# nRF9160_Thing_Plus.net
KiCad netlist of a schematic drawn in EAGLE
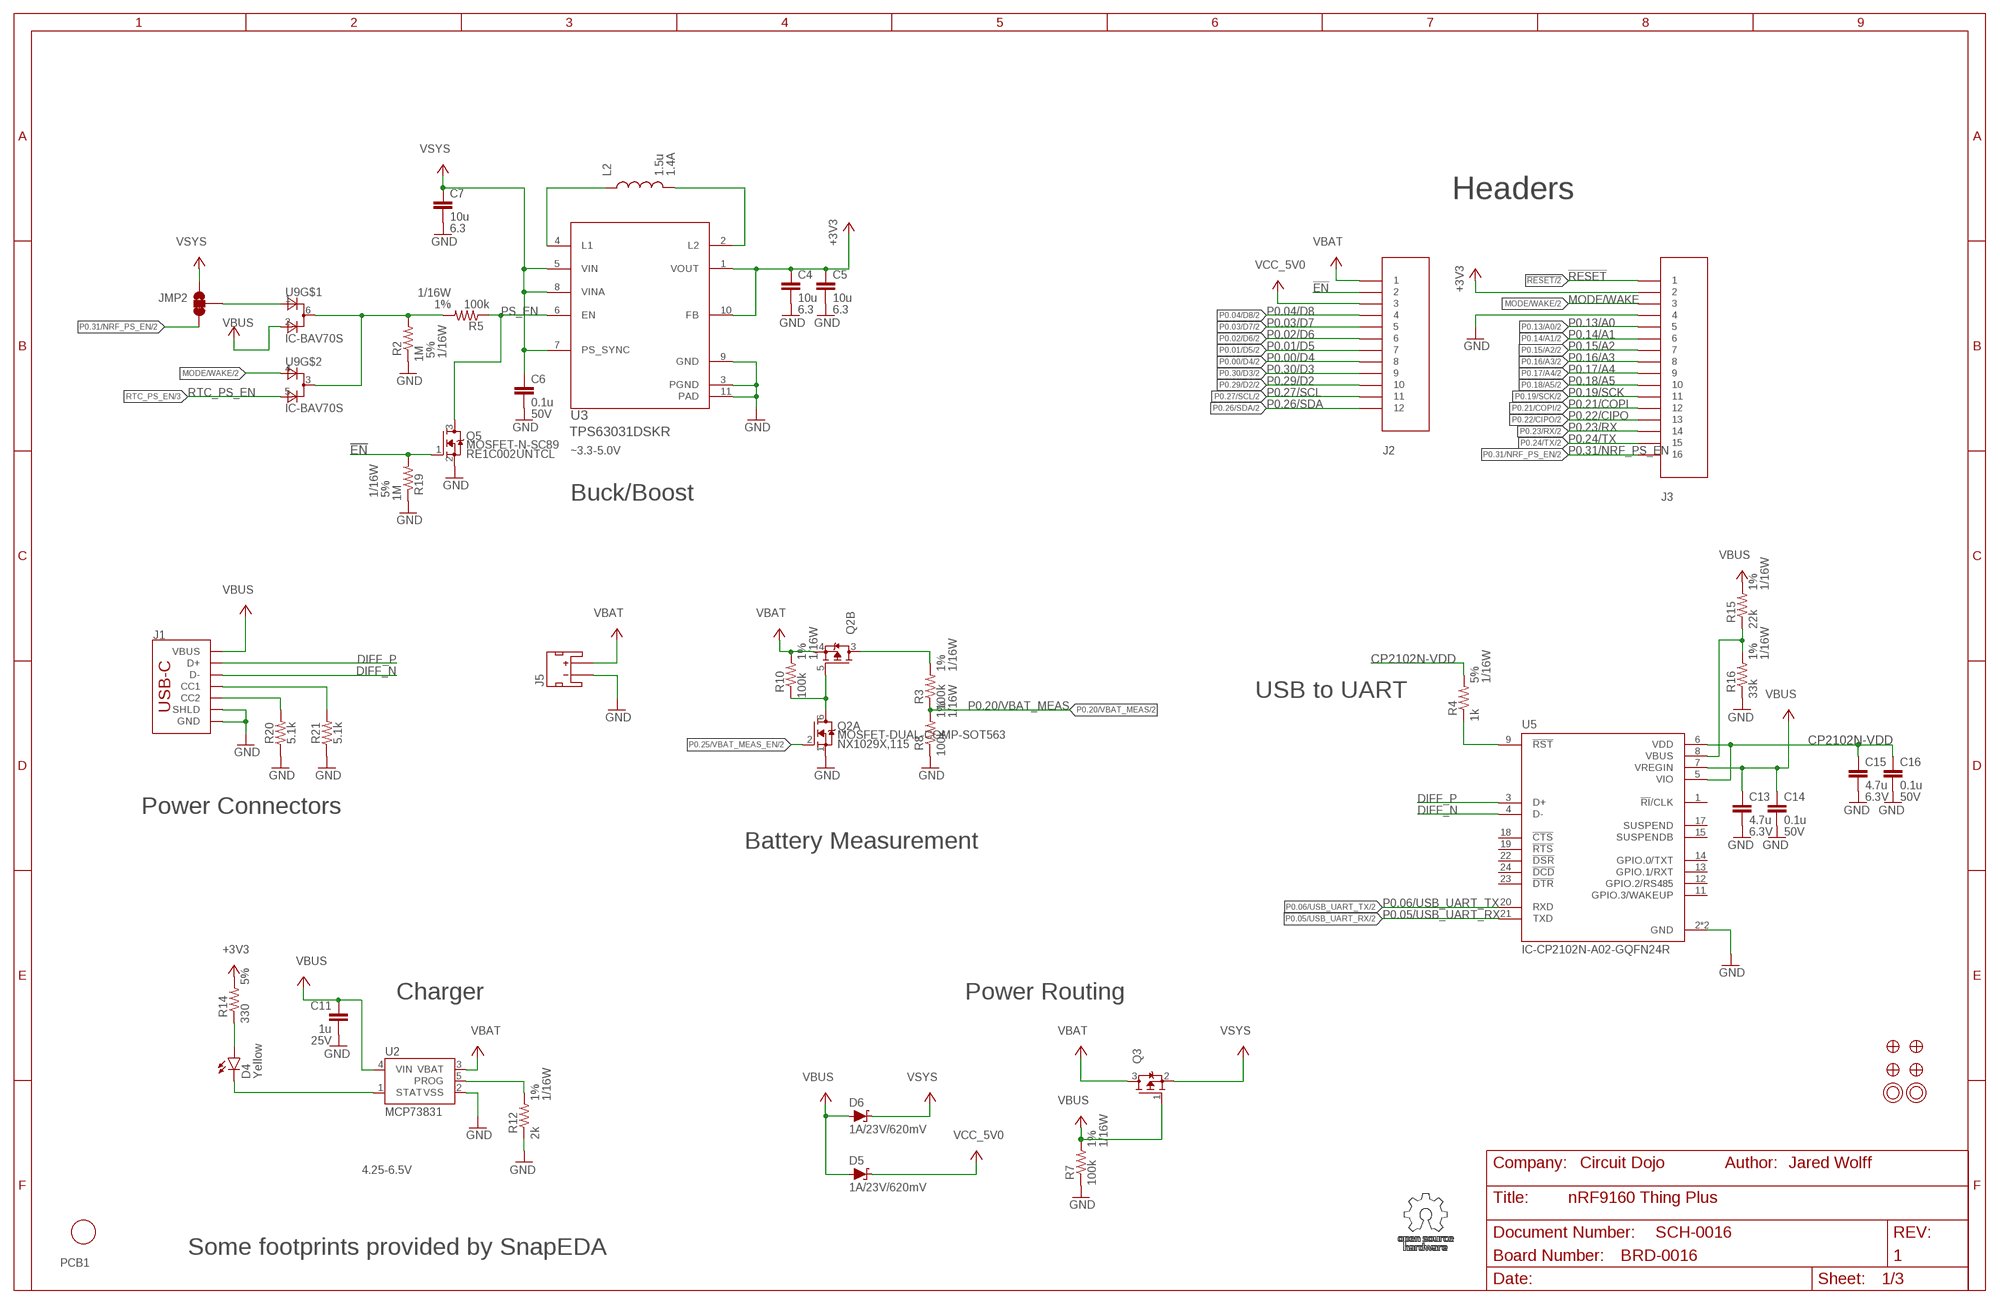
[diagram p0: schematic, sheet 1]
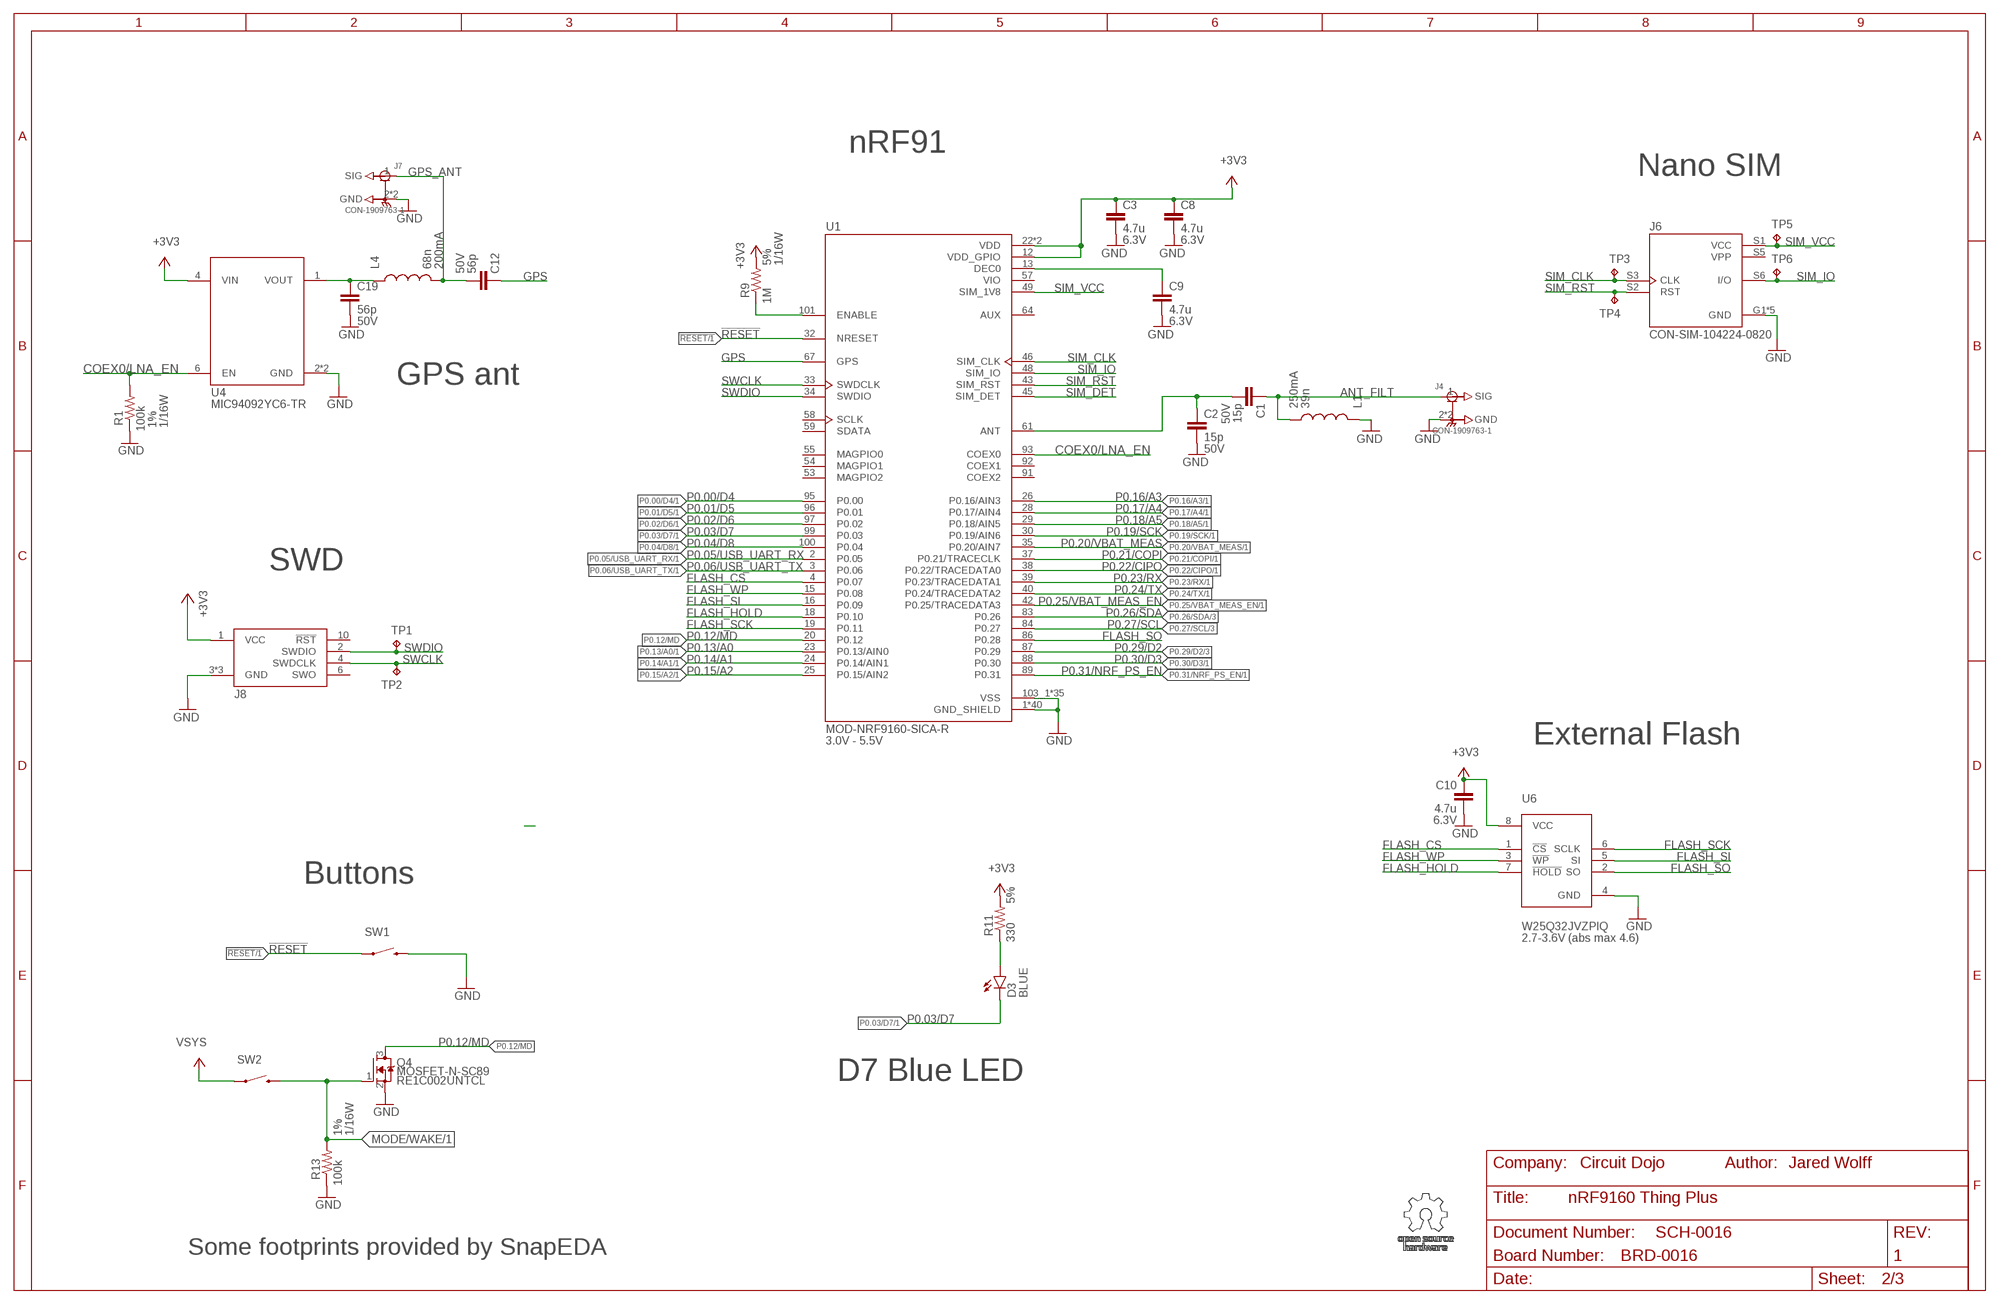
[diagram p1: schematic, sheet 2]
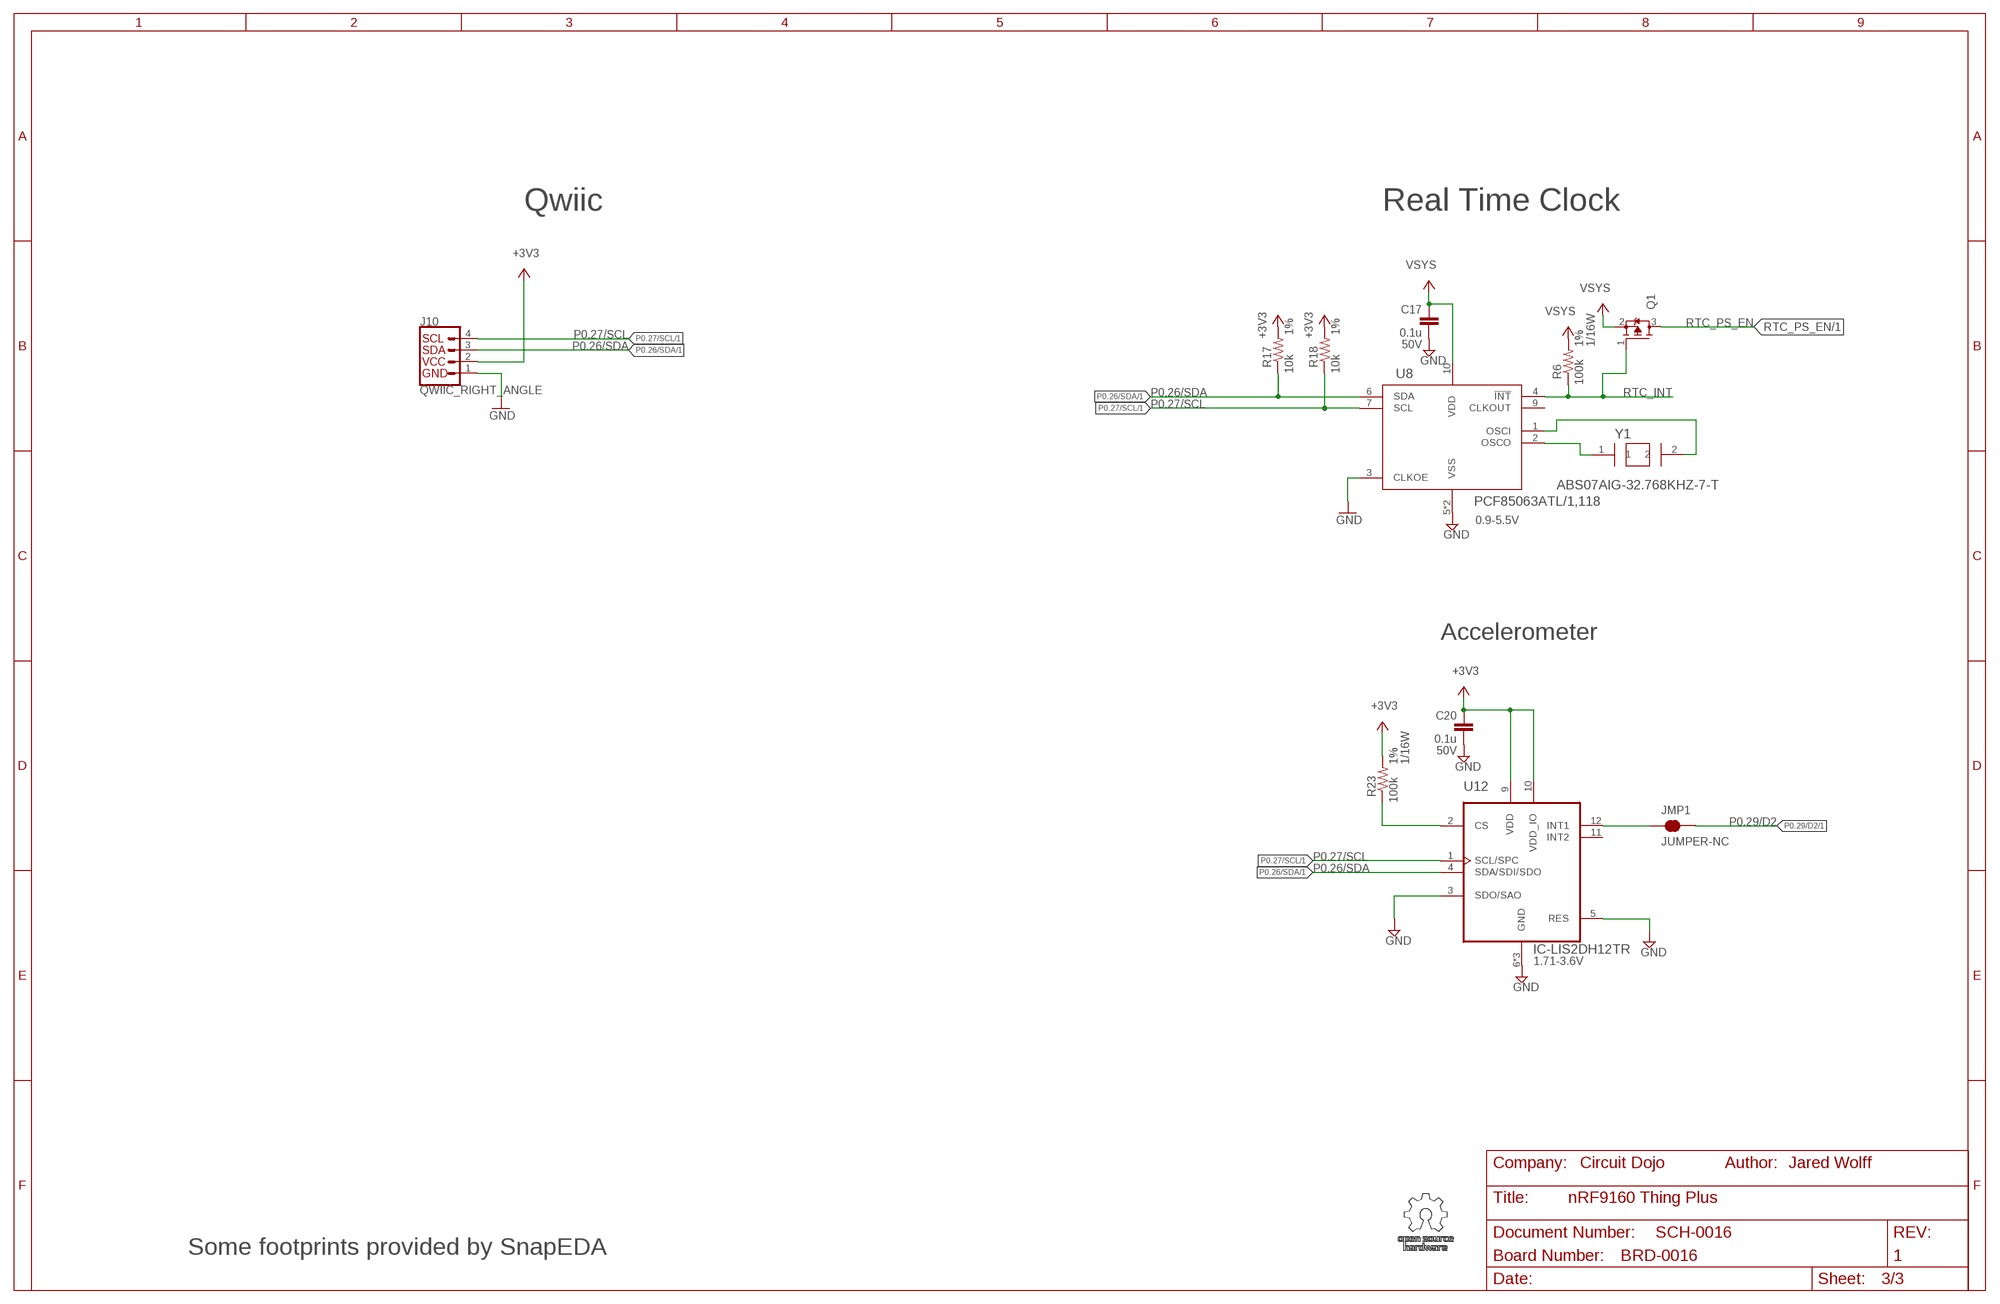
[diagram p2: schematic, sheet 3]

(export (version "E")
  (design (tool "Eeschema 10.0.6"))
  (components
    (comp (ref "C1")
      (value "15p")
      (footprint "eagle-import:CAPC1005X55N")
      (fields
        (field (name "MF") "Yageo")
        (field (name "MPN") "CC0402JRNPO9BN150")
        (field (name "VOLTHIGH") "50V")
      )
      (libsource (lib "eagle-import") (part "CAP-0402-15P-50V"))
    )
    (comp (ref "C2")
      (value "15p")
      (footprint "eagle-import:CAPC1005X55N")
      (fields
        (field (name "MF") "Yageo")
        (field (name "MPN") "CC0402JRNPO9BN150")
        (field (name "VOLTHIGH") "50V")
      )
      (libsource (lib "eagle-import") (part "CAP-0402-15P-50V"))
    )
    (comp (ref "C3")
      (value "4.7u")
      (footprint "eagle-import:C0603")
      (fields (field (name "MPN") "JMK107BB7475MA-T") (field (name "VOLTHIGH") "6.3V"))
      (libsource (lib "eagle-import") (part "CAP-0603-4.7U-6.3V-2"))
    )
    (comp (ref "C8")
      (value "4.7u")
      (footprint "eagle-import:C0603")
      (fields (field (name "MPN") "JMK107BB7475MA-T") (field (name "VOLTHIGH") "6.3V"))
      (libsource (lib "eagle-import") (part "CAP-0603-4.7U-6.3V-2"))
    )
    (comp (ref "C9")
      (value "4.7u")
      (footprint "eagle-import:C0603")
      (fields (field (name "MPN") "JMK107BB7475MA-T") (field (name "VOLTHIGH") "6.3V"))
      (libsource (lib "eagle-import") (part "CAP-0603-4.7U-6.3V-2"))
    )
    (comp (ref "C10")
      (value "4.7u")
      (footprint "eagle-import:C0603")
      (fields (field (name "MPN") "JMK107BB7475MA-T") (field (name "VOLTHIGH") "6.3V"))
      (libsource (lib "eagle-import") (part "CAP-0603-4.7U-6.3V-2"))
    )
    (comp (ref "C12")
      (value "56p")
      (footprint "eagle-import:CAPC1005X55N")
      (fields
        (field (name "MF") "Kemet")
        (field (name "MPN") "C0402C560J5GACTU‎")
        (field (name "VOLTHIGH") "50V")
      )
      (libsource (lib "eagle-import") (part "CAP-0402-56PF-50V"))
    )
    (comp (ref "C19")
      (value "56p")
      (footprint "eagle-import:CAPC1005X55N")
      (fields
        (field (name "MF") "Kemet")
        (field (name "MPN") "C0402C560J5GACTU‎")
        (field (name "VOLTHIGH") "50V")
      )
      (libsource (lib "eagle-import") (part "CAP-0402-56PF-50V"))
    )
    (comp (ref "D3")
      (value "BLUE")
      (footprint "eagle-import:LED-0603")
      (libsource (lib "eagle-import") (part "LED-BLUE0603"))
    )
    (comp (ref "J4")
      (value "CON-1909763-1")
      (footprint "eagle-import:TE_1909763-1")
      (fields (field (name "MF") "TE Connectivity") (field (name "MPN") "1909763-1"))
      (libsource (lib "eagle-import") (part "CON-1909763-1"))
    )
    (comp (ref "J6")
      (value "CON-SIM-104224-0820")
      (footprint "eagle-import:MOLEX_104224-0820")
      (fields (field (name "MF") "Molex") (field (name "MPN") "104224-0820"))
      (libsource (lib "eagle-import") (part "CON-SIM-104224-0820"))
    )
    (comp (ref "J7")
      (value "CON-1909763-1")
      (footprint "eagle-import:TE_1909763-1")
      (fields (field (name "MF") "TE Connectivity") (field (name "MPN") "1909763-1"))
      (libsource (lib "eagle-import") (part "CON-1909763-1"))
    )
    (comp (ref "J8")
      (value "CON-FTSH-105-XX-X-DV")
      (footprint "eagle-import:SAMTEC_FTSH-105-XX-X-DV")
      (fields (field (name "MF") "Samtec") (field (name "MPN") "FTSH-105-01-F-DV-K"))
      (libsource (lib "eagle-import") (part "CON-FTSH-105-XX-X-DV"))
    )
    (comp (ref "L1")
      (value "39n")
      (footprint "eagle-import:IND0402_22N_TAI")
      (fields (field (name "CURRENT") "250mA") (field (name "MPN") "LQG15HN39NJ02D"))
      (libsource (lib "eagle-import") (part "IND-0402-39NH-250MA"))
    )
    (comp (ref "L4")
      (value "68n")
      (footprint "eagle-import:IND0402_22N_TAI")
      (fields (field (name "CURRENT") "200mA") (field (name "MPN") "LQG15HN68NH02D‎"))
      (libsource (lib "eagle-import") (part "IND-0402-68NH-200MA"))
    )
    (comp (ref "Q4")
      (value "MOSFET-N-SC89")
      (footprint "eagle-import:DIO_RB558WMF-L")
      (fields (field (name "MPN") "RE1C002UNTCL") (field (name "MF") "Rohm Semiconductor"))
      (libsource (lib "eagle-import") (part "MOSFET-N-SC89"))
    )
    (comp (ref "R1")
      (value "100k")
      (footprint "eagle-import:R0402-M")
      (fields
        (field (name "MPN") "RC0402FR07100KL")
        (field (name "POWER") "1/16W")
        (field (name "TOLERANCE") "1%")
      )
      (libsource (lib "eagle-import") (part "RES-0402-100K-1%"))
    )
    (comp (ref "R9")
      (value "1M")
      (footprint "eagle-import:R0402-M")
      (fields
        (field (name "MPN") "RC0402JR-071ML")
        (field (name "POWER") "1/16W")
        (field (name "TOLERANCE") "5%")
      )
      (libsource (lib "eagle-import") (part "RES-0402-1M-5%"))
    )
    (comp (ref "R11")
      (value "330")
      (footprint "eagle-import:R0402-M")
      (fields
        (field (name "MF") "Yageo")
        (field (name "MPN") "RC0402JR-07330RL")
        (field (name "TOLERANCE") "5%")
      )
      (libsource (lib "eagle-import") (part "RES-0402-330-5%"))
    )
    (comp (ref "R13")
      (value "100k")
      (footprint "eagle-import:R0402-M")
      (fields
        (field (name "MPN") "RC0402FR07100KL")
        (field (name "POWER") "1/16W")
        (field (name "TOLERANCE") "1%")
      )
      (libsource (lib "eagle-import") (part "RES-0402-100K-1%"))
    )
    (comp (ref "SW1")
      (value "MOMENTARY-SWITCH-SPST-SMD-4.6X2.8MM")
      (footprint "eagle-import:TACTILE_SWITCH_SMD_4.6X2.8MM")
      (libsource (lib "eagle-import") (part "MOMENTARY-SWITCH-SPST-SMD-4.6X2.8MM"))
    )
    (comp (ref "SW2")
      (value "MOMENTARY-SWITCH-SPST-SMD-4.6X2.8MM")
      (footprint "eagle-import:TACTILE_SWITCH_SMD_4.6X2.8MM")
      (libsource (lib "eagle-import") (part "MOMENTARY-SWITCH-SPST-SMD-4.6X2.8MM"))
    )
    (comp (ref "TP1")
      (value "TP-1SIDE-1P0")
      (footprint "eagle-import:TP-1P0")
      (libsource (lib "eagle-import") (part "TP-1SIDE-1P0"))
    )
    (comp (ref "TP2")
      (value "TP-1SIDE-1P0")
      (footprint "eagle-import:TP-1P0")
      (libsource (lib "eagle-import") (part "TP-1SIDE-1P0"))
    )
    (comp (ref "TP3")
      (value "TP-1SIDE-1P0")
      (footprint "eagle-import:TP-1P0")
      (libsource (lib "eagle-import") (part "TP-1SIDE-1P0"))
    )
    (comp (ref "TP4")
      (value "TP-1SIDE-1P0")
      (footprint "eagle-import:TP-1P0")
      (libsource (lib "eagle-import") (part "TP-1SIDE-1P0"))
    )
    (comp (ref "TP5")
      (value "TP-1SIDE-1P0")
      (footprint "eagle-import:TP-1P0")
      (libsource (lib "eagle-import") (part "TP-1SIDE-1P0"))
    )
    (comp (ref "TP6")
      (value "TP-1SIDE-1P0")
      (footprint "eagle-import:TP-1P0")
      (libsource (lib "eagle-import") (part "TP-1SIDE-1P0"))
    )
    (comp (ref "U1")
      (value "MOD-NRF9160-SICA-R")
      (footprint "eagle-import:NORDIC_NRF9160-SICA-R")
      (fields (field (name "MF") "Nordic Semiconductor") (field (name "MPN") "NRF9160-SICA-R"))
      (libsource (lib "eagle-import") (part "MOD-NRF9160-SICA-R"))
    )
    (comp (ref "U4")
      (value "POWER-SWITCH-MIC94092YC6")
      (footprint "eagle-import:SOT363")
      (fields (field (name "MPN") "MIC94092YC6-TR"))
      (libsource (lib "eagle-import") (part "POWER-SWITCH-MIC94092YC6"))
    )
    (comp (ref "U6")
      (value "FLASH-WSON")
      (footprint "eagle-import:WIN_ZP-8-L")
      (fields (field (name "MPN") "W25Q32JVZPIQ"))
      (libsource (lib "eagle-import") (part "FLASH-WSON-W25Q32JVZPIQ"))
    )
    (comp (ref "C4")
      (value "10u")
      (footprint "eagle-import:C0603")
      (fields (field (name "MPN") "JMK107ABJ106MA-T") (field (name "VOLTHIGH") "6.3"))
      (libsource (lib "eagle-import") (part "CAP-0603-10U-6.3V"))
    )
    (comp (ref "C5")
      (value "10u")
      (footprint "eagle-import:C0603")
      (fields (field (name "MPN") "JMK107ABJ106MA-T") (field (name "VOLTHIGH") "6.3"))
      (libsource (lib "eagle-import") (part "CAP-0603-10U-6.3V"))
    )
    (comp (ref "C6")
      (value "0.1u")
      (footprint "eagle-import:CAPC1005X55N")
      (fields
        (field (name "MF") "Taiyo Yuden")
        (field (name "MPN") "UMK105BJ104KV-F")
        (field (name "VOLTHIGH") "50V")
      )
      (libsource (lib "eagle-import") (part "CAP-0402-0.1U-50V"))
    )
    (comp (ref "C7")
      (value "10u")
      (footprint "eagle-import:C0603")
      (fields (field (name "MPN") "JMK107ABJ106MA-T") (field (name "VOLTHIGH") "6.3"))
      (libsource (lib "eagle-import") (part "CAP-0603-10U-6.3V"))
    )
    (comp (ref "C11")
      (value "1u")
      (footprint "eagle-import:CAPC1005X55N")
      (fields
        (field (name "MF") "TDK")
        (field (name "MPN") "C1005X5R1E105M050BC")
        (field (name "VOLTHIGH") "25V")
      )
      (libsource (lib "eagle-import") (part "CAP-0402-1U-25V-1"))
    )
    (comp (ref "C13")
      (value "4.7u")
      (footprint "eagle-import:C0603")
      (fields (field (name "MPN") "JMK107BB7475MA-T") (field (name "VOLTHIGH") "6.3V"))
      (libsource (lib "eagle-import") (part "CAP-0603-4.7U-6.3V-2"))
    )
    (comp (ref "C14")
      (value "0.1u")
      (footprint "eagle-import:CAPC1005X55N")
      (fields
        (field (name "MF") "Taiyo Yuden")
        (field (name "MPN") "UMK105BJ104KV-F")
        (field (name "VOLTHIGH") "50V")
      )
      (libsource (lib "eagle-import") (part "CAP-0402-0.1U-50V"))
    )
    (comp (ref "C15")
      (value "4.7u")
      (footprint "eagle-import:C0603")
      (fields (field (name "MPN") "JMK107BB7475MA-T") (field (name "VOLTHIGH") "6.3V"))
      (libsource (lib "eagle-import") (part "CAP-0603-4.7U-6.3V-2"))
    )
    (comp (ref "C16")
      (value "0.1u")
      (footprint "eagle-import:CAPC1005X55N")
      (fields
        (field (name "MF") "Taiyo Yuden")
        (field (name "MPN") "UMK105BJ104KV-F")
        (field (name "VOLTHIGH") "50V")
      )
      (libsource (lib "eagle-import") (part "CAP-0402-0.1U-50V"))
    )
    (comp (ref "D4")
      (value "Yellow")
      (footprint "eagle-import:LED-0603")
      (libsource (lib "eagle-import") (part "LED-YELLOW0603"))
    )
    (comp (ref "D5")
      (value "1A/23V/620mV")
      (footprint "eagle-import:SOD-323")
      (libsource (lib "eagle-import") (part "DIODE-SCHOTTKY-BAT20J"))
    )
    (comp (ref "D6")
      (value "1A/23V/620mV")
      (footprint "eagle-import:SOD-323")
      (libsource (lib "eagle-import") (part "DIODE-SCHOTTKY-BAT20J"))
    )
    (comp (ref "J1")
      (value "USB Female C")
      (footprint "eagle-import:USB-C-16P_4LAYER-PADS")
      (libsource (lib "eagle-import") (part "USB_C_4-LAYER_PADS"))
    )
    (comp (ref "J2")
      (value "CON-HEADER-1X12-MALE-PIN")
      (footprint "eagle-import:CON-HEADER-1X12-MALE-PIN")
      (libsource (lib "eagle-import") (part "CON-HEADER-1X12-MALE-PIN"))
    )
    (comp (ref "J3")
      (value "CON-HEADER-1X16-MALE-PIN")
      (footprint "eagle-import:CON-HEADER-1X16-MALE-PIN")
      (libsource (lib "eagle-import") (part "CON-HEADER-1X16-MALE-PIN"))
    )
    (comp (ref "J5")
      (value "JST_2MM_MALE")
      (footprint "eagle-import:JST-2-SMD")
      (libsource (lib "eagle-import") (part "JST_2MM_MALE"))
    )
    (comp (ref "JMP2")
      (value "JUMPER-3/1")
      (footprint "eagle-import:JUMPER-ROUND-3-NO-R")
      (libsource (lib "eagle-import") (part "JUMPER-3/1"))
    )
    (comp (ref "L2")
      (value "1.5u")
      (footprint "eagle-import:IND-2P0X2P0X1P2")
      (fields (field (name "CURRENT") "1.4A") (field (name "MPN") "NRV2012T1R5NGF"))
      (libsource (lib "eagle-import") (part "IND-1.5U-1.4A-2X2"))
    )
    (comp (ref "PCB1")
      (value "PCB-NRF91-FEATHER")
      (footprint "eagle-import:PLACEHOLDER")
      (fields (field (name "MPN") "BRD-0015"))
      (libsource (lib "eagle-import") (part "PCB-NRF91-FEATHER"))
    )
    (comp (ref "Q2")
      (value "MOSFET-DUAL-COMP-SOT563")
      (footprint "eagle-import:SOT50P160X60-6N")
      (fields (field (name "MPN") "NX1029X,115"))
      (libsource (lib "eagle-import") (part "MOSFET-DUAL-COMP-SOT563"))
    )
    (comp (ref "Q3")
      (value "MOSFET-P-20V-4.7A-SOT23")
      (footprint "eagle-import:SOT23")
      (fields (field (name "MPN") "TSM500P02CX RFG"))
      (libsource (lib "eagle-import") (part "MOSFET-P-SOT23-20V-4.7A"))
    )
    (comp (ref "Q5")
      (value "MOSFET-N-SC89")
      (footprint "eagle-import:DIO_RB558WMF-L")
      (fields (field (name "MPN") "RE1C002UNTCL") (field (name "MF") "Rohm Semiconductor"))
      (libsource (lib "eagle-import") (part "MOSFET-N-SC89"))
    )
    (comp (ref "R2")
      (value "1M")
      (footprint "eagle-import:R0402-M")
      (fields
        (field (name "MPN") "RC0402JR-071ML")
        (field (name "POWER") "1/16W")
        (field (name "TOLERANCE") "5%")
      )
      (libsource (lib "eagle-import") (part "RES-0402-1M-5%"))
    )
    (comp (ref "R3")
      (value "100k")
      (footprint "eagle-import:R0402-M")
      (fields
        (field (name "MPN") "RC0402FR07100KL")
        (field (name "POWER") "1/16W")
        (field (name "TOLERANCE") "1%")
      )
      (libsource (lib "eagle-import") (part "RES-0402-100K-1%"))
    )
    (comp (ref "R4")
      (value "1k")
      (footprint "eagle-import:R0402-M")
      (fields
        (field (name "MPN") "RC0402JR-071KL")
        (field (name "POWER") "1/16W")
        (field (name "TOLERANCE") "5%")
      )
      (libsource (lib "eagle-import") (part "RES-0402-1K-5%"))
    )
    (comp (ref "R5")
      (value "100k")
      (footprint "eagle-import:R0402-M")
      (fields
        (field (name "MPN") "RC0402FR07100KL")
        (field (name "POWER") "1/16W")
        (field (name "TOLERANCE") "1%")
      )
      (libsource (lib "eagle-import") (part "RES-0402-100K-1%"))
    )
    (comp (ref "R7")
      (value "100k")
      (footprint "eagle-import:R0402-M")
      (fields
        (field (name "MPN") "RC0402FR07100KL")
        (field (name "POWER") "1/16W")
        (field (name "TOLERANCE") "1%")
      )
      (libsource (lib "eagle-import") (part "RES-0402-100K-1%"))
    )
    (comp (ref "R8")
      (value "100k")
      (footprint "eagle-import:R0402-M")
      (fields
        (field (name "MPN") "RC0402FR07100KL")
        (field (name "POWER") "1/16W")
        (field (name "TOLERANCE") "1%")
      )
      (libsource (lib "eagle-import") (part "RES-0402-100K-1%"))
    )
    (comp (ref "R10")
      (value "100k")
      (footprint "eagle-import:R0402-M")
      (fields
        (field (name "MPN") "RC0402FR07100KL")
        (field (name "POWER") "1/16W")
        (field (name "TOLERANCE") "1%")
      )
      (libsource (lib "eagle-import") (part "RES-0402-100K-1%"))
    )
    (comp (ref "R12")
      (value "2k")
      (footprint "eagle-import:R0402-M")
      (fields
        (field (name "MPN") "RC0402FR-072KL")
        (field (name "POWER") "1/16W")
        (field (name "TOLERANCE") "1%")
      )
      (libsource (lib "eagle-import") (part "RES-0402-2K-1%"))
    )
    (comp (ref "R14")
      (value "330")
      (footprint "eagle-import:R0402-M")
      (fields
        (field (name "MF") "Yageo")
        (field (name "MPN") "RC0402JR-07330RL")
        (field (name "TOLERANCE") "5%")
      )
      (libsource (lib "eagle-import") (part "RES-0402-330-5%"))
    )
    (comp (ref "R15")
      (value "22k")
      (footprint "eagle-import:R0402-M")
      (fields
        (field (name "MF") "Yageo")
        (field (name "MPN") "RC0402FR-0722KL")
        (field (name "POWER") "1/16W")
        (field (name "TOLERANCE") "1%")
      )
      (libsource (lib "eagle-import") (part "RES-0402-22K-1%"))
    )
    (comp (ref "R16")
      (value "33k")
      (footprint "eagle-import:R0402-M")
      (fields
        (field (name "MF") "Yageo")
        (field (name "MPN") "RC0402FR-0722KL")
        (field (name "POWER") "1/16W")
        (field (name "TOLERANCE") "1%")
      )
      (libsource (lib "eagle-import") (part "RES-0402-33K-1%"))
    )
    (comp (ref "R19")
      (value "1M")
      (footprint "eagle-import:R0402-M")
      (fields
        (field (name "MPN") "RC0402JR-071ML")
        (field (name "POWER") "1/16W")
        (field (name "TOLERANCE") "5%")
      )
      (libsource (lib "eagle-import") (part "RES-0402-1M-5%"))
    )
    (comp (ref "R20")
      (value "5.1k")
      (footprint "eagle-import:0402-TIGHT")
      (libsource (lib "eagle-import") (part "5.1KOHM-0402T-1/16W-1%"))
    )
    (comp (ref "R21")
      (value "5.1k")
      (footprint "eagle-import:0402-TIGHT")
      (libsource (lib "eagle-import") (part "5.1KOHM-0402T-1/16W-1%"))
    )
    (comp (ref "U$3")
      (value "FIDUCIAL-1MM")
      (footprint "eagle-import:FIDUCIAL-1MM")
      (libsource (lib "eagle-import") (part "FIDUCIAL-1MM"))
    )
    (comp (ref "U$4")
      (value "FIDUCIAL-1MM")
      (footprint "eagle-import:FIDUCIAL-1MM")
      (libsource (lib "eagle-import") (part "FIDUCIAL-1MM"))
    )
    (comp (ref "U$24")
      (value "FIDUCIAL-1MM")
      (footprint "eagle-import:FIDUCIAL-1MM")
      (libsource (lib "eagle-import") (part "FIDUCIAL-1MM"))
    )
    (comp (ref "U$31")
      (value "MOUNTING-HOLE-2.5MM-PLATED")
      (footprint "eagle-import:MOUNTING-HOLE-2.5MM-PLATED")
      (libsource (lib "eagle-import") (part "MOUNTING-HOLE-2.5MM-PLATED"))
    )
    (comp (ref "U$32")
      (value "MOUNTING-HOLE-2.5MM-PLATED")
      (footprint "eagle-import:MOUNTING-HOLE-2.5MM-PLATED")
      (libsource (lib "eagle-import") (part "MOUNTING-HOLE-2.5MM-PLATED"))
    )
    (comp (ref "U$35")
      (value "FIDUCIAL-1MM")
      (footprint "eagle-import:FIDUCIAL-1MM")
      (libsource (lib "eagle-import") (part "FIDUCIAL-1MM"))
    )
    (comp (ref "U2")
      (value "MCP73831")
      (footprint "eagle-import:SOT23-5")
      (libsource (lib "eagle-import") (part "MCP73831"))
    )
    (comp (ref "U3")
      (value "IC-TPS63031DSKR")
      (footprint "eagle-import:DSK0010A")
      (fields (field (name "MF") "Texas Instruments") (field (name "MPN") "TPS63031DSKR"))
      (libsource (lib "eagle-import") (part "IC-TPS63031DSKR"))
    )
    (comp (ref "U5")
      (value "IC-CP2102N-A02-GQFN24R")
      (footprint "eagle-import:QFN50P400X400X80-25N")
      (fields (field (name "MF") "Silicon Labs") (field (name "MPN") "CP2102N-A02-GQFN24R"))
      (libsource (lib "eagle-import") (part "IC-CP2102N-A02-GQFN24R"))
    )
    (comp (ref "U9")
      (value "IC-BAV70S")
      (footprint "eagle-import:SOT363")
      (fields (field (name "MF") "Nexperia USA Inc.") (field (name "MPN") "BAV70S,115"))
      (libsource (lib "eagle-import") (part "IC-BAV70S"))
    )
    (comp (ref "C17")
      (value "0.1u")
      (footprint "eagle-import:CAPC1005X55N")
      (fields
        (field (name "MF") "Taiyo Yuden")
        (field (name "MPN") "UMK105BJ104KV-F")
        (field (name "VOLTHIGH") "50V")
      )
      (libsource (lib "eagle-import") (part "CAP-0402-0.1U-50V"))
    )
    (comp (ref "C20")
      (value "0.1u")
      (footprint "eagle-import:CAPC1005X55N")
      (fields
        (field (name "MF") "Taiyo Yuden")
        (field (name "MPN") "UMK105BJ104KV-F")
        (field (name "VOLTHIGH") "50V")
      )
      (libsource (lib "eagle-import") (part "CAP-0402-0.1U-50V"))
    )
    (comp (ref "J10")
      (value "QWIIC_RIGHT_ANGLE")
      (footprint "eagle-import:JST04_1MM_RA")
      (libsource (lib "eagle-import") (part "QWIIC_CONNECTORJS-1MM"))
    )
    (comp (ref "JMP1")
      (value "JUMPER-NC")
      (footprint "eagle-import:JUMPER-ROUND-NC")
      (libsource (lib "eagle-import") (part "JUMPER-NC"))
    )
    (comp (ref "Q1")
      (value "MOSFET-P-SC89")
      (footprint "eagle-import:DIO_RB558WMF-L")
      (fields (field (name "MPN") "RE1C001ZPTL"))
      (libsource (lib "eagle-import") (part "MOSFET-P-SC89"))
    )
    (comp (ref "R6")
      (value "100k")
      (footprint "eagle-import:R0402-M")
      (fields
        (field (name "MPN") "RC0402FR07100KL")
        (field (name "POWER") "1/16W")
        (field (name "TOLERANCE") "1%")
      )
      (libsource (lib "eagle-import") (part "RES-0402-100K-1%"))
    )
    (comp (ref "R17")
      (value "10k")
      (footprint "eagle-import:R0402-M")
      (fields (field (name "MPN") "RC0603FR-0710KL") (field (name "TOLERANCE") "1%"))
      (libsource (lib "eagle-import") (part "RES-0402-10K-1%"))
    )
    (comp (ref "R18")
      (value "10k")
      (footprint "eagle-import:R0402-M")
      (fields (field (name "MPN") "RC0603FR-0710KL") (field (name "TOLERANCE") "1%"))
      (libsource (lib "eagle-import") (part "RES-0402-10K-1%"))
    )
    (comp (ref "R23")
      (value "100k")
      (footprint "eagle-import:R0402-M")
      (fields
        (field (name "MPN") "RC0402FR07100KL")
        (field (name "POWER") "1/16W")
        (field (name "TOLERANCE") "1%")
      )
      (libsource (lib "eagle-import") (part "RES-0402-100K-1%"))
    )
    (comp (ref "U8")
      (value "IC-PCF85063ATL/1")
      (footprint "eagle-import:DFN10_2P7X2P7-L")
      (fields (field (name "MPN") "PCF85063ATL/1,118") (field (name "MF") "NXP"))
      (libsource (lib "eagle-import") (part "IC-PCF85063ATL/1"))
    )
    (comp (ref "U12")
      (value "IC-LIS2DH12TR")
      (footprint "eagle-import:PQFN50P200X200100-12N")
      (fields (field (name "MF") "STMicroelectronics") (field (name "MPN") "LIS2DH12TR"))
      (libsource (lib "eagle-import") (part "IC-LIS2DH12TR"))
    )
    (comp (ref "Y1")
      (value "XTAL-ABS07AIG-32.768KHZ-7-T")
      (footprint "eagle-import:XTAL320X150X90")
      (fields (field (name "MPN") "ABS07AIG-32.768KHZ-7-T") (field (name "MF") "Abracon"))
      (libsource (lib "eagle-import") (part "XTAL-ABS07AIG-32.768KHZ-7-T"))
    )
  )
  (nets
    (net (code "1") (name "+3V3") (class "Default")
      (node (ref "C10") (pin "1") (pinfunction "1_1") (pintype "passive"))
      (node (ref "C20") (pin "1") (pinfunction "1_1") (pintype "passive"))
      (node (ref "C3") (pin "1") (pinfunction "1_1") (pintype "passive"))
      (node (ref "C4") (pin "1") (pinfunction "1_1") (pintype "passive"))
      (node (ref "C5") (pin "1") (pinfunction "1_1") (pintype "passive"))
      (node (ref "C8") (pin "1") (pinfunction "1_1") (pintype "passive"))
      (node (ref "J10") (pin "2") (pinfunction "2_2") (pintype "power_in"))
      (node (ref "J3") (pin "2") (pinfunction "2_2") (pintype "bidirectional"))
      (node (ref "J8") (pin "1") (pinfunction "VCC_1") (pintype "bidirectional"))
      (node (ref "R11") (pin "2") (pinfunction "2_2") (pintype "passive"))
      (node (ref "R14") (pin "2") (pinfunction "2_2") (pintype "passive"))
      (node (ref "R17") (pin "2") (pinfunction "2_2") (pintype "passive"))
      (node (ref "R18") (pin "2") (pinfunction "2_2") (pintype "passive"))
      (node (ref "R23") (pin "2") (pinfunction "2_2") (pintype "passive"))
      (node (ref "R9") (pin "2") (pinfunction "2_2") (pintype "passive"))
      (node (ref "U1") (pin "102") (pinfunction "VDD_102") (pintype "power_in"))
      (node (ref "U1") (pin "12") (pinfunction "VDD_GPIO_12") (pintype "power_in"))
      (node (ref "U1") (pin "22") (pinfunction "VDD_22") (pintype "power_in"))
      (node (ref "U12") (pin "10") (pinfunction "VDD_IO_10") (pintype "power_in"))
      (node (ref "U12") (pin "9") (pinfunction "VDD_9") (pintype "power_in"))
      (node (ref "U3") (pin "1") (pinfunction "VOUT_1") (pintype "power_in"))
      (node (ref "U3") (pin "10") (pinfunction "FB_10") (pintype "input"))
      (node (ref "U4") (pin "4") (pinfunction "VIN_4") (pintype "power_in"))
      (node (ref "U6") (pin "8") (pinfunction "VCC_8") (pintype "bidirectional"))
    )
    (net (code "2") (name "ANT_FILT") (class "Default")
      (node (ref "C1") (pin "1") (pinfunction "1_1") (pintype "passive"))
      (node (ref "J4") (pin "1") (pinfunction "SIG_1") (pintype "passive"))
      (node (ref "L1") (pin "2") (pinfunction "2_2") (pintype "passive"))
    )
    (net (code "3") (name "COEX0{slash}LNA_EN") (class "Default")
      (node (ref "R1") (pin "2") (pinfunction "2_2") (pintype "passive"))
      (node (ref "U1") (pin "93") (pinfunction "COEX0_93") (pintype "bidirectional"))
      (node (ref "U4") (pin "6") (pinfunction "EN_6") (pintype "input"))
    )
    (net (code "4") (name "CP2102N-VDD") (class "Default")
      (node (ref "C15") (pin "1") (pinfunction "1_1") (pintype "passive"))
      (node (ref "C16") (pin "1") (pinfunction "1_1") (pintype "passive"))
      (node (ref "R4") (pin "2") (pinfunction "2_2") (pintype "passive"))
      (node (ref "U5") (pin "5") (pinfunction "VIO_5") (pintype "power_in"))
      (node (ref "U5") (pin "6") (pinfunction "VDD_6") (pintype "power_in"))
    )
    (net (code "5") (name "DIFF_N") (class "Default")
      (node (ref "J1") (pin "A7") (pinfunction "D-_A7") (pintype "bidirectional"))
      (node (ref "J1") (pin "B7") (pinfunction "D-_B7") (pintype "bidirectional"))
      (node (ref "U5") (pin "4") (pinfunction "D-_4") (pintype "bidirectional"))
    )
    (net (code "6") (name "DIFF_P") (class "Default")
      (node (ref "J1") (pin "A6") (pinfunction "D+_A6") (pintype "bidirectional"))
      (node (ref "J1") (pin "B6") (pinfunction "D+_B6") (pintype "bidirectional"))
      (node (ref "U5") (pin "3") (pinfunction "D+_3") (pintype "bidirectional"))
    )
    (net (code "7") (name "FLASH_CS") (class "Default")
      (node (ref "U1") (pin "4") (pinfunction "P0.07_4") (pintype "bidirectional"))
      (node (ref "U6") (pin "1") (pinfunction "~{CS}_1") (pintype "bidirectional"))
    )
    (net (code "8") (name "FLASH_HOLD") (class "Default")
      (node (ref "U1") (pin "18") (pinfunction "P0.10_18") (pintype "bidirectional"))
      (node (ref "U6") (pin "7") (pinfunction "~{HOLD}_7") (pintype "bidirectional"))
    )
    (net (code "9") (name "FLASH_SCK") (class "Default")
      (node (ref "U1") (pin "19") (pinfunction "P0.11_19") (pintype "bidirectional"))
      (node (ref "U6") (pin "6") (pinfunction "SCLK_6") (pintype "bidirectional"))
    )
    (net (code "10") (name "FLASH_SI") (class "Default")
      (node (ref "U1") (pin "16") (pinfunction "P0.09_16") (pintype "bidirectional"))
      (node (ref "U6") (pin "5") (pinfunction "SI_5") (pintype "bidirectional"))
    )
    (net (code "11") (name "FLASH_SO") (class "Default")
      (node (ref "U1") (pin "86") (pinfunction "P0.28_86") (pintype "bidirectional"))
      (node (ref "U6") (pin "2") (pinfunction "SO_2") (pintype "bidirectional"))
    )
    (net (code "12") (name "FLASH_WP") (class "Default")
      (node (ref "U1") (pin "15") (pinfunction "P0.08_15") (pintype "bidirectional"))
      (node (ref "U6") (pin "3") (pinfunction "~{WP}_3") (pintype "bidirectional"))
    )
    (net (code "13") (name "GND") (class "Default")
      (node (ref "C10") (pin "2") (pinfunction "2_2") (pintype "passive"))
      (node (ref "C11") (pin "2") (pinfunction "2_2") (pintype "passive"))
      (node (ref "C13") (pin "2") (pinfunction "2_2") (pintype "passive"))
      (node (ref "C14") (pin "2") (pinfunction "2_2") (pintype "passive"))
      (node (ref "C15") (pin "2") (pinfunction "2_2") (pintype "passive"))
      (node (ref "C16") (pin "2") (pinfunction "2_2") (pintype "passive"))
      (node (ref "C17") (pin "2") (pinfunction "2_2") (pintype "passive"))
      (node (ref "C19") (pin "2") (pinfunction "2_2") (pintype "passive"))
      (node (ref "C2") (pin "2") (pinfunction "2_2") (pintype "passive"))
      (node (ref "C20") (pin "2") (pinfunction "2_2") (pintype "passive"))
      (node (ref "C3") (pin "2") (pinfunction "2_2") (pintype "passive"))
      (node (ref "C4") (pin "2") (pinfunction "2_2") (pintype "passive"))
      (node (ref "C5") (pin "2") (pinfunction "2_2") (pintype "passive"))
      (node (ref "C6") (pin "2") (pinfunction "2_2") (pintype "passive"))
      (node (ref "C7") (pin "2") (pinfunction "2_2") (pintype "passive"))
      (node (ref "C8") (pin "2") (pinfunction "2_2") (pintype "passive"))
      (node (ref "C9") (pin "2") (pinfunction "2_2") (pintype "passive"))
      (node (ref "J1") (pin "GND") (pinfunction "GND_GND") (pintype "bidirectional"))
      (node (ref "J1") (pin "GND2") (pinfunction "GND_GND2") (pintype "bidirectional"))
      (node (ref "J1") (pin "SHLD1") (pinfunction "SHLD_SHLD1") (pintype "bidirectional"))
      (node (ref "J1") (pin "SHLD2") (pinfunction "SHLD_SHLD2") (pintype "bidirectional"))
      (node (ref "J1") (pin "SHLD3") (pinfunction "SHLD_SHLD3") (pintype "bidirectional"))
      (node (ref "J1") (pin "SHLD4") (pinfunction "SHLD_SHLD4") (pintype "bidirectional"))
      (node (ref "J10") (pin "1") (pinfunction "1_1") (pintype "power_in"))
      (node (ref "J3") (pin "4") (pinfunction "4_4") (pintype "bidirectional"))
      (node (ref "J4") (pin "2") (pinfunction "GND_2") (pintype "passive"))
      (node (ref "J4") (pin "3") (pinfunction "GND_3") (pintype "passive"))
      (node (ref "J5") (pin "1") (pinfunction "-_1") (pintype "bidirectional"))
      (node (ref "J6") (pin "G1") (pinfunction "GND_G1") (pintype "power_in"))
      (node (ref "J6") (pin "G2") (pinfunction "GND_G2") (pintype "power_in"))
      (node (ref "J6") (pin "G3") (pinfunction "GND_G3") (pintype "power_in"))
      (node (ref "J6") (pin "G4") (pinfunction "GND_G4") (pintype "power_in"))
      (node (ref "J6") (pin "S4") (pinfunction "GND_S4") (pintype "power_in"))
      (node (ref "J7") (pin "2") (pinfunction "GND_2") (pintype "passive"))
      (node (ref "J7") (pin "3") (pinfunction "GND_3") (pintype "passive"))
      (node (ref "J8") (pin "3") (pinfunction "GND_3") (pintype "bidirectional"))
      (node (ref "J8") (pin "5") (pinfunction "GND_5") (pintype "bidirectional"))
      (node (ref "J8") (pin "9") (pinfunction "GND_9") (pintype "bidirectional"))
      (node (ref "L1") (pin "1") (pinfunction "1_1") (pintype "passive"))
      (node (ref "Q2") (pin "1") (pinfunction "S_1") (pintype "bidirectional"))
      (node (ref "Q4") (pin "2") (pinfunction "S_2") (pintype "bidirectional"))
      (node (ref "Q5") (pin "2") (pinfunction "S_2") (pintype "bidirectional"))
      (node (ref "R1") (pin "1") (pinfunction "1_1") (pintype "passive"))
      (node (ref "R12") (pin "1") (pinfunction "1_1") (pintype "passive"))
      (node (ref "R13") (pin "1") (pinfunction "1_1") (pintype "passive"))
      (node (ref "R16") (pin "1") (pinfunction "1_1") (pintype "passive"))
      (node (ref "R19") (pin "1") (pinfunction "1_1") (pintype "passive"))
      (node (ref "R2") (pin "1") (pinfunction "1_1") (pintype "passive"))
      (node (ref "R20") (pin "1") (pinfunction "1_1") (pintype "passive"))
      (node (ref "R21") (pin "1") (pinfunction "1_1") (pintype "passive"))
      (node (ref "R7") (pin "1") (pinfunction "1_1") (pintype "passive"))
      (node (ref "R8") (pin "1") (pinfunction "1_1") (pintype "passive"))
      (node (ref "SW1") (pin "3") (pinfunction "2_3") (pintype "passive"))
      (node (ref "SW1") (pin "4") (pinfunction "2_4") (pintype "passive"))
      (node (ref "U1") (pin "1") (pinfunction "GND_SHIELD_1") (pintype "power_in"))
      (node (ref "U1") (pin "103_1") (pinfunction "VSS_103_1") (pintype "power_in"))
      (node (ref "U1") (pin "103_10") (pinfunction "VSS_103_10") (pintype "power_in"))
      (node (ref "U1") (pin "103_11") (pinfunction "VSS_103_11") (pintype "power_in"))
      (node (ref "U1") (pin "103_12") (pinfunction "VSS_103_12") (pintype "power_in"))
      (node (ref "U1") (pin "103_13") (pinfunction "VSS_103_13") (pintype "power_in"))
      (node (ref "U1") (pin "103_14") (pinfunction "VSS_103_14") (pintype "power_in"))
      (node (ref "U1") (pin "103_15") (pinfunction "VSS_103_15") (pintype "power_in"))
      (node (ref "U1") (pin "103_16") (pinfunction "VSS_103_16") (pintype "power_in"))
      (node (ref "U1") (pin "103_17") (pinfunction "VSS_103_17") (pintype "power_in"))
      (node (ref "U1") (pin "103_18") (pinfunction "VSS_103_18") (pintype "power_in"))
      (node (ref "U1") (pin "103_19") (pinfunction "VSS_103_19") (pintype "power_in"))
      (node (ref "U1") (pin "103_2") (pinfunction "VSS_103_2") (pintype "power_in"))
      (node (ref "U1") (pin "103_20") (pinfunction "VSS_103_20") (pintype "power_in"))
      (node (ref "U1") (pin "103_21") (pinfunction "VSS_103_21") (pintype "power_in"))
      (node (ref "U1") (pin "103_22") (pinfunction "VSS_103_22") (pintype "power_in"))
      (node (ref "U1") (pin "103_23") (pinfunction "VSS_103_23") (pintype "power_in"))
      (node (ref "U1") (pin "103_24") (pinfunction "VSS_103_24") (pintype "power_in"))
      (node (ref "U1") (pin "103_25") (pinfunction "VSS_103_25") (pintype "power_in"))
      (node (ref "U1") (pin "103_26") (pinfunction "VSS_103_26") (pintype "power_in"))
      (node (ref "U1") (pin "103_27") (pinfunction "VSS_103_27") (pintype "power_in"))
      (node (ref "U1") (pin "103_28") (pinfunction "VSS_103_28") (pintype "power_in"))
      (node (ref "U1") (pin "103_29") (pinfunction "VSS_103_29") (pintype "power_in"))
      (node (ref "U1") (pin "103_3") (pinfunction "VSS_103_3") (pintype "power_in"))
      (node (ref "U1") (pin "103_30") (pinfunction "VSS_103_30") (pintype "power_in"))
      (node (ref "U1") (pin "103_31") (pinfunction "VSS_103_31") (pintype "power_in"))
      (node (ref "U1") (pin "103_32") (pinfunction "VSS_103_32") (pintype "power_in"))
      (node (ref "U1") (pin "103_33") (pinfunction "VSS_103_33") (pintype "power_in"))
      (node (ref "U1") (pin "103_34") (pinfunction "VSS_103_34") (pintype "power_in"))
      (node (ref "U1") (pin "103_35") (pinfunction "VSS_103_35") (pintype "power_in"))
      (node (ref "U1") (pin "103_4") (pinfunction "VSS_103_4") (pintype "power_in"))
      (node (ref "U1") (pin "103_5") (pinfunction "VSS_103_5") (pintype "power_in"))
      (node (ref "U1") (pin "103_6") (pinfunction "VSS_103_6") (pintype "power_in"))
      (node (ref "U1") (pin "103_7") (pinfunction "VSS_103_7") (pintype "power_in"))
      (node (ref "U1") (pin "103_8") (pinfunction "VSS_103_8") (pintype "power_in"))
      (node (ref "U1") (pin "103_9") (pinfunction "VSS_103_9") (pintype "power_in"))
      (node (ref "U1") (pin "11") (pinfunction "GND_SHIELD_11") (pintype "power_in"))
      (node (ref "U1") (pin "14") (pinfunction "GND_SHIELD_14") (pintype "power_in"))
      (node (ref "U1") (pin "17") (pinfunction "GND_SHIELD_17") (pintype "power_in"))
      (node (ref "U1") (pin "21") (pinfunction "GND_SHIELD_21") (pintype "power_in"))
      (node (ref "U1") (pin "27") (pinfunction "GND_SHIELD_27") (pintype "power_in"))
      (node (ref "U1") (pin "31") (pinfunction "GND_SHIELD_31") (pintype "power_in"))
      (node (ref "U1") (pin "36") (pinfunction "GND_SHIELD_36") (pintype "power_in"))
      (node (ref "U1") (pin "41") (pinfunction "GND_SHIELD_41") (pintype "power_in"))
      (node (ref "U1") (pin "44") (pinfunction "GND_SHIELD_44") (pintype "power_in"))
      (node (ref "U1") (pin "47") (pinfunction "GND_SHIELD_47") (pintype "power_in"))
      (node (ref "U1") (pin "5") (pinfunction "GND_SHIELD_5") (pintype "power_in"))
      (node (ref "U1") (pin "50") (pinfunction "GND_SHIELD_50") (pintype "power_in"))
      (node (ref "U1") (pin "52") (pinfunction "GND_SHIELD_52") (pintype "power_in"))
      (node (ref "U1") (pin "56") (pinfunction "GND_SHIELD_56") (pintype "power_in"))
      (node (ref "U1") (pin "6") (pinfunction "GND_SHIELD_6") (pintype "power_in"))
      (node (ref "U1") (pin "60") (pinfunction "GND_SHIELD_60") (pintype "power_in"))
      (node (ref "U1") (pin "62") (pinfunction "GND_SHIELD_62") (pintype "power_in"))
      (node (ref "U1") (pin "63") (pinfunction "GND_SHIELD_63") (pintype "power_in"))
      (node (ref "U1") (pin "65") (pinfunction "GND_SHIELD_65") (pintype "power_in"))
      (node (ref "U1") (pin "66") (pinfunction "GND_SHIELD_66") (pintype "power_in"))
      (node (ref "U1") (pin "68") (pinfunction "GND_SHIELD_68") (pintype "power_in"))
      (node (ref "U1") (pin "69") (pinfunction "GND_SHIELD_69") (pintype "power_in"))
      (node (ref "U1") (pin "7") (pinfunction "GND_SHIELD_7") (pintype "power_in"))
      (node (ref "U1") (pin "72") (pinfunction "GND_SHIELD_72") (pintype "power_in"))
      (node (ref "U1") (pin "74") (pinfunction "GND_SHIELD_74") (pintype "power_in"))
      (node (ref "U1") (pin "75") (pinfunction "GND_SHIELD_75") (pintype "power_in"))
      (node (ref "U1") (pin "76") (pinfunction "GND_SHIELD_76") (pintype "power_in"))
      (node (ref "U1") (pin "77") (pinfunction "GND_SHIELD_77") (pintype "power_in"))
      (node (ref "U1") (pin "78") (pinfunction "GND_SHIELD_78") (pintype "power_in"))
      (node (ref "U1") (pin "79") (pinfunction "GND_SHIELD_79") (pintype "power_in"))
      (node (ref "U1") (pin "8") (pinfunction "GND_SHIELD_8") (pintype "power_in"))
      (node (ref "U1") (pin "80") (pinfunction "GND_SHIELD_80") (pintype "power_in"))
      (node (ref "U1") (pin "81") (pinfunction "GND_SHIELD_81") (pintype "power_in"))
      (node (ref "U1") (pin "82") (pinfunction "GND_SHIELD_82") (pintype "power_in"))
      (node (ref "U1") (pin "85") (pinfunction "GND_SHIELD_85") (pintype "power_in"))
      (node (ref "U1") (pin "9") (pinfunction "GND_SHIELD_9") (pintype "power_in"))
      (node (ref "U1") (pin "90") (pinfunction "GND_SHIELD_90") (pintype "power_in"))
      (node (ref "U1") (pin "94") (pinfunction "GND_SHIELD_94") (pintype "power_in"))
      (node (ref "U1") (pin "98") (pinfunction "GND_SHIELD_98") (pintype "power_in"))
      (node (ref "U12") (pin "3") (pinfunction "SDO/SAO_3") (pintype "bidirectional"))
      (node (ref "U12") (pin "5") (pinfunction "RES_5") (pintype "power_in"))
      (node (ref "U12") (pin "6") (pinfunction "GND_6") (pintype "power_in"))
      (node (ref "U12") (pin "7") (pinfunction "GND_7") (pintype "power_in"))
      (node (ref "U12") (pin "8") (pinfunction "GND_8") (pintype "power_in"))
      (node (ref "U2") (pin "2") (pinfunction "VSS_2") (pintype "power_in"))
      (node (ref "U3") (pin "11") (pinfunction "PAD_11") (pintype "power_in"))
      (node (ref "U3") (pin "3") (pinfunction "PGND_3") (pintype "power_in"))
      (node (ref "U3") (pin "9") (pinfunction "GND_9") (pintype "power_in"))
      (node (ref "U4") (pin "2") (pinfunction "GND_2") (pintype "power_in"))
      (node (ref "U4") (pin "5") (pinfunction "GND_5") (pintype "power_in"))
      (node (ref "U5") (pin "2") (pinfunction "GND_2") (pintype "power_in"))
      (node (ref "U5") (pin "25") (pinfunction "GND_25") (pintype "power_in"))
      (node (ref "U6") (pin "4") (pinfunction "GND_4") (pintype "bidirectional"))
      (node (ref "U8") (pin "11") (pinfunction "VSS_11") (pintype "power_in"))
      (node (ref "U8") (pin "3") (pinfunction "CLKOE_3") (pintype "input"))
      (node (ref "U8") (pin "5") (pinfunction "VSS_5") (pintype "power_in"))
    )
    (net (code "14") (name "GPS") (class "Default")
      (node (ref "C12") (pin "1") (pinfunction "1_1") (pintype "passive"))
      (node (ref "U1") (pin "67") (pinfunction "GPS_67") (pintype "input"))
    )
    (net (code "15") (name "GPS_ANT") (class "Default")
      (node (ref "C12") (pin "2") (pinfunction "2_2") (pintype "passive"))
      (node (ref "J7") (pin "1") (pinfunction "SIG_1") (pintype "passive"))
      (node (ref "L4") (pin "2") (pinfunction "2_2") (pintype "passive"))
    )
    (net (code "16") (name "MODE{slash}WAKE") (class "Default")
      (node (ref "J3") (pin "3") (pinfunction "3_3") (pintype "bidirectional"))
      (node (ref "Q4") (pin "1") (pinfunction "G_1") (pintype "bidirectional"))
      (node (ref "R13") (pin "2") (pinfunction "2_2") (pintype "passive"))
      (node (ref "SW2") (pin "3") (pinfunction "2_3") (pintype "passive"))
      (node (ref "SW2") (pin "4") (pinfunction "2_4") (pintype "passive"))
      (node (ref "U9") (pin "4") (pinfunction "A1_4") (pintype "passive"))
    )
    (net (code "17") (name "Net-(D3-PadA)") (class "Default")
      (node (ref "D3") (pin "A") (pinfunction "A_A") (pintype "passive"))
      (node (ref "R11") (pin "1") (pinfunction "1_1") (pintype "passive"))
    )
    (net (code "18") (name "Net-(D4-PadA)") (class "Default")
      (node (ref "D4") (pin "A") (pinfunction "A_A") (pintype "passive"))
      (node (ref "R14") (pin "1") (pinfunction "1_1") (pintype "passive"))
    )
    (net (code "19") (name "Net-(J1-CC1)") (class "Default")
      (node (ref "J1") (pin "A5") (pinfunction "CC1_A5") (pintype "bidirectional"))
      (node (ref "R21") (pin "2") (pinfunction "2_2") (pintype "passive"))
    )
    (net (code "20") (name "Net-(J1-CC2)") (class "Default")
      (node (ref "J1") (pin "B5") (pinfunction "CC2_B5") (pintype "bidirectional"))
      (node (ref "R20") (pin "2") (pinfunction "2_2") (pintype "passive"))
    )
    (net (code "21") (name "Net-(JMP1-1)") (class "Default")
      (node (ref "JMP1") (pin "P$1") (pinfunction "1_P$1") (pintype "passive"))
      (node (ref "U12") (pin "12") (pinfunction "INT1_12") (pintype "output"))
    )
    (net (code "22") (name "Net-(JMP2-2)") (class "Default")
      (node (ref "JMP2") (pin "P$2") (pinfunction "2_P$2") (pintype "passive"))
      (node (ref "U9") (pin "1") (pinfunction "A1_1") (pintype "passive"))
    )
    (net (code "23") (name "Net-(L2-1)") (class "Default")
      (node (ref "L2") (pin "P$1") (pinfunction "1_P$1") (pintype "passive"))
      (node (ref "U3") (pin "4") (pinfunction "L1_4") (pintype "passive"))
    )
    (net (code "24") (name "Net-(L2-2)") (class "Default")
      (node (ref "L2") (pin "P$2") (pinfunction "2_P$2") (pintype "passive"))
      (node (ref "U3") (pin "2") (pinfunction "L2_2") (pintype "passive"))
    )
    (net (code "25") (name "Net-(Q2A-D)") (class "Default")
      (node (ref "Q2") (pin "5") (pinfunction "G_5") (pintype "passive"))
      (node (ref "Q2") (pin "6") (pinfunction "D_6") (pintype "bidirectional"))
      (node (ref "R10") (pin "1") (pinfunction "1_1") (pintype "passive"))
    )
    (net (code "26") (name "Net-(Q2B-D)") (class "Default")
      (node (ref "Q2") (pin "3") (pinfunction "D_3") (pintype "passive"))
      (node (ref "R3") (pin "2") (pinfunction "2_2") (pintype "passive"))
    )
    (net (code "27") (name "Net-(U1-ANT)") (class "Default")
      (node (ref "C1") (pin "2") (pinfunction "2_2") (pintype "passive"))
      (node (ref "C2") (pin "1") (pinfunction "1_1") (pintype "passive"))
      (node (ref "U1") (pin "61") (pinfunction "ANT_61") (pintype "bidirectional"))
    )
    (net (code "28") (name "Net-(U1-DEC0)") (class "Default")
      (node (ref "C9") (pin "1") (pinfunction "1_1") (pintype "passive"))
      (node (ref "U1") (pin "13") (pinfunction "DEC0_13") (pintype "power_in"))
    )
    (net (code "29") (name "Net-(U1-ENABLE)") (class "Default")
      (node (ref "R9") (pin "1") (pinfunction "1_1") (pintype "passive"))
      (node (ref "U1") (pin "101") (pinfunction "ENABLE_101") (pintype "input"))
    )
    (net (code "30") (name "Net-(U2-PROG)") (class "Default")
      (node (ref "R12") (pin "2") (pinfunction "2_2") (pintype "passive"))
      (node (ref "U2") (pin "5") (pinfunction "PROG_5") (pintype "input"))
    )
    (net (code "31") (name "Net-(U2-STAT)") (class "Default")
      (node (ref "D4") (pin "C") (pinfunction "C_C") (pintype "passive"))
      (node (ref "U2") (pin "1") (pinfunction "STAT_1") (pintype "output"))
    )
    (net (code "32") (name "Net-(U4-VOUT)") (class "Default")
      (node (ref "C19") (pin "1") (pinfunction "1_1") (pintype "passive"))
      (node (ref "L4") (pin "1") (pinfunction "1_1") (pintype "passive"))
      (node (ref "U4") (pin "1") (pinfunction "VOUT_1") (pintype "power_in"))
    )
    (net (code "33") (name "Net-(U5-VBUS)") (class "Default")
      (node (ref "R15") (pin "1") (pinfunction "1_1") (pintype "passive"))
      (node (ref "R16") (pin "2") (pinfunction "2_2") (pintype "passive"))
      (node (ref "U5") (pin "8") (pinfunction "VBUS_8") (pintype "input"))
    )
    (net (code "34") (name "Net-(U5-~{RST})") (class "Default")
      (node (ref "R4") (pin "1") (pinfunction "1_1") (pintype "passive"))
      (node (ref "U5") (pin "9") (pinfunction "~{RST}_9") (pintype "bidirectional"))
    )
    (net (code "35") (name "Net-(U8-OSCI)") (class "Default")
      (node (ref "U8") (pin "1") (pinfunction "OSCI_1") (pintype "input"))
      (node (ref "Y1") (pin "2") (pinfunction "2_2") (pintype "passive"))
    )
    (net (code "36") (name "Net-(U8-OSCO)") (class "Default")
      (node (ref "U8") (pin "2") (pinfunction "OSCO_2") (pintype "output"))
      (node (ref "Y1") (pin "1") (pinfunction "1_1") (pintype "passive"))
    )
    (net (code "37") (name "Net-(U9A-C)") (class "Default")
      (node (ref "R2") (pin "2") (pinfunction "2_2") (pintype "passive"))
      (node (ref "R5") (pin "2") (pinfunction "2_2") (pintype "passive"))
      (node (ref "U9") (pin "3") (pinfunction "C_3") (pintype "passive"))
      (node (ref "U9") (pin "6") (pinfunction "C_6") (pintype "passive"))
    )
    (net (code "38") (name "Net-(U12-CS)") (class "Default")
      (node (ref "R23") (pin "1") (pinfunction "1_1") (pintype "passive"))
      (node (ref "U12") (pin "2") (pinfunction "CS_2") (pintype "input"))
    )
    (net (code "39") (name "P0.00{slash}D4") (class "Default")
      (node (ref "J2") (pin "8") (pinfunction "8_8") (pintype "bidirectional"))
      (node (ref "U1") (pin "95") (pinfunction "P0.00_95") (pintype "bidirectional"))
    )
    (net (code "40") (name "P0.01{slash}D5") (class "Default")
      (node (ref "J2") (pin "7") (pinfunction "7_7") (pintype "bidirectional"))
      (node (ref "U1") (pin "96") (pinfunction "P0.01_96") (pintype "bidirectional"))
    )
    (net (code "41") (name "P0.02{slash}D6") (class "Default")
      (node (ref "J2") (pin "6") (pinfunction "6_6") (pintype "bidirectional"))
      (node (ref "U1") (pin "97") (pinfunction "P0.02_97") (pintype "bidirectional"))
    )
    (net (code "42") (name "P0.03{slash}D7") (class "Default")
      (node (ref "D3") (pin "C") (pinfunction "C_C") (pintype "passive"))
      (node (ref "J2") (pin "5") (pinfunction "5_5") (pintype "bidirectional"))
      (node (ref "U1") (pin "99") (pinfunction "P0.03_99") (pintype "bidirectional"))
    )
    (net (code "43") (name "P0.04{slash}D8") (class "Default")
      (node (ref "J2") (pin "4") (pinfunction "4_4") (pintype "bidirectional"))
      (node (ref "U1") (pin "100") (pinfunction "P0.04_100") (pintype "bidirectional"))
    )
    (net (code "44") (name "P0.05{slash}USB_UART_RX") (class "Default")
      (node (ref "U1") (pin "2") (pinfunction "P0.05_2") (pintype "bidirectional"))
      (node (ref "U5") (pin "21") (pinfunction "TXD_21") (pintype "output"))
    )
    (net (code "45") (name "P0.06{slash}USB_UART_TX") (class "Default")
      (node (ref "U1") (pin "3") (pinfunction "P0.06_3") (pintype "bidirectional"))
      (node (ref "U5") (pin "20") (pinfunction "RXD_20") (pintype "input"))
    )
    (net (code "46") (name "P0.12{slash}MD") (class "Default")
      (node (ref "Q4") (pin "3") (pinfunction "D_3") (pintype "bidirectional"))
      (node (ref "U1") (pin "20") (pinfunction "P0.12_20") (pintype "bidirectional"))
    )
    (net (code "47") (name "P0.13{slash}A0") (class "Default")
      (node (ref "J3") (pin "5") (pinfunction "5_5") (pintype "bidirectional"))
      (node (ref "U1") (pin "23") (pinfunction "P0.13/AIN0_23") (pintype "bidirectional"))
    )
    (net (code "48") (name "P0.14{slash}A1") (class "Default")
      (node (ref "J3") (pin "6") (pinfunction "6_6") (pintype "bidirectional"))
      (node (ref "U1") (pin "24") (pinfunction "P0.14/AIN1_24") (pintype "bidirectional"))
    )
    (net (code "49") (name "P0.15{slash}A2") (class "Default")
      (node (ref "J3") (pin "7") (pinfunction "7_7") (pintype "bidirectional"))
      (node (ref "U1") (pin "25") (pinfunction "P0.15/AIN2_25") (pintype "bidirectional"))
    )
    (net (code "50") (name "P0.16{slash}A3") (class "Default")
      (node (ref "J3") (pin "8") (pinfunction "8_8") (pintype "bidirectional"))
      (node (ref "U1") (pin "26") (pinfunction "P0.16/AIN3_26") (pintype "bidirectional"))
    )
    (net (code "51") (name "P0.17{slash}A4") (class "Default")
      (node (ref "J3") (pin "9") (pinfunction "9_9") (pintype "bidirectional"))
      (node (ref "U1") (pin "28") (pinfunction "P0.17/AIN4_28") (pintype "bidirectional"))
    )
    (net (code "52") (name "P0.18{slash}A5") (class "Default")
      (node (ref "J3") (pin "10") (pinfunction "10_10") (pintype "bidirectional"))
      (node (ref "U1") (pin "29") (pinfunction "P0.18/AIN5_29") (pintype "bidirectional"))
    )
    (net (code "53") (name "P0.19{slash}SCK") (class "Default")
      (node (ref "J3") (pin "11") (pinfunction "11_11") (pintype "bidirectional"))
      (node (ref "U1") (pin "30") (pinfunction "P0.19/AIN6_30") (pintype "bidirectional"))
    )
    (net (code "54") (name "P0.20{slash}VBAT_MEAS") (class "Default")
      (node (ref "R3") (pin "1") (pinfunction "1_1") (pintype "passive"))
      (node (ref "R8") (pin "2") (pinfunction "2_2") (pintype "passive"))
      (node (ref "U1") (pin "35") (pinfunction "P0.20/AIN7_35") (pintype "bidirectional"))
    )
    (net (code "55") (name "P0.21{slash}COPI") (class "Default")
      (node (ref "J3") (pin "12") (pinfunction "12_12") (pintype "bidirectional"))
      (node (ref "U1") (pin "37") (pinfunction "P0.21/TRACECLK_37") (pintype "bidirectional"))
    )
    (net (code "56") (name "P0.22{slash}CIPO") (class "Default")
      (node (ref "J3") (pin "13") (pinfunction "13_13") (pintype "bidirectional"))
      (node (ref "U1") (pin "38") (pinfunction "P0.22/TRACEDATA0_38") (pintype "bidirectional"))
    )
    (net (code "57") (name "P0.23{slash}RX") (class "Default")
      (node (ref "J3") (pin "14") (pinfunction "14_14") (pintype "bidirectional"))
      (node (ref "U1") (pin "39") (pinfunction "P0.23/TRACEDATA1_39") (pintype "bidirectional"))
    )
    (net (code "58") (name "P0.24{slash}TX") (class "Default")
      (node (ref "J3") (pin "15") (pinfunction "15_15") (pintype "bidirectional"))
      (node (ref "U1") (pin "40") (pinfunction "P0.24/TRACEDATA2_40") (pintype "bidirectional"))
    )
    (net (code "59") (name "P0.25{slash}VBAT_MEAS_EN") (class "Default")
      (node (ref "Q2") (pin "2") (pinfunction "G_2") (pintype "bidirectional"))
      (node (ref "U1") (pin "42") (pinfunction "P0.25/TRACEDATA3_42") (pintype "bidirectional"))
    )
    (net (code "60") (name "P0.26{slash}SDA") (class "Default")
      (node (ref "J10") (pin "3") (pinfunction "3_3") (pintype "passive"))
      (node (ref "J2") (pin "12") (pinfunction "12_12") (pintype "bidirectional"))
      (node (ref "R17") (pin "1") (pinfunction "1_1") (pintype "passive"))
      (node (ref "U1") (pin "83") (pinfunction "P0.26_83") (pintype "bidirectional"))
      (node (ref "U12") (pin "4") (pinfunction "SDA/SDI/SDO_4") (pintype "bidirectional"))
      (node (ref "U8") (pin "6") (pinfunction "SDA_6") (pintype "bidirectional"))
    )
    (net (code "61") (name "P0.27{slash}SCL") (class "Default")
      (node (ref "J10") (pin "4") (pinfunction "4_4") (pintype "passive"))
      (node (ref "J2") (pin "11") (pinfunction "11_11") (pintype "bidirectional"))
      (node (ref "R18") (pin "1") (pinfunction "1_1") (pintype "passive"))
      (node (ref "U1") (pin "84") (pinfunction "P0.27_84") (pintype "bidirectional"))
      (node (ref "U12") (pin "1") (pinfunction "SCL/SPC_1") (pintype "bidirectional"))
      (node (ref "U8") (pin "7") (pinfunction "SCL_7") (pintype "input"))
    )
    (net (code "62") (name "P0.29{slash}D2") (class "Default")
      (node (ref "J2") (pin "10") (pinfunction "10_10") (pintype "bidirectional"))
      (node (ref "JMP1") (pin "P$2") (pinfunction "2_P$2") (pintype "passive"))
      (node (ref "U1") (pin "87") (pinfunction "P0.29_87") (pintype "bidirectional"))
    )
    (net (code "63") (name "P0.30{slash}D3") (class "Default")
      (node (ref "J2") (pin "9") (pinfunction "9_9") (pintype "bidirectional"))
      (node (ref "U1") (pin "88") (pinfunction "P0.30_88") (pintype "bidirectional"))
    )
    (net (code "64") (name "P0.31{slash}NRF_PS_EN") (class "Default")
      (node (ref "J3") (pin "16") (pinfunction "16_16") (pintype "bidirectional"))
      (node (ref "JMP2") (pin "P$3") (pinfunction "3_P$3") (pintype "passive"))
      (node (ref "U1") (pin "89") (pinfunction "P0.31_89") (pintype "bidirectional"))
    )
    (net (code "65") (name "PS_EN") (class "Default")
      (node (ref "Q5") (pin "3") (pinfunction "D_3") (pintype "bidirectional"))
      (node (ref "R5") (pin "1") (pinfunction "1_1") (pintype "passive"))
      (node (ref "U3") (pin "6") (pinfunction "EN_6") (pintype "input"))
    )
    (net (code "66") (name "RTC_INT") (class "Default")
      (node (ref "Q1") (pin "1") (pinfunction "G_1") (pintype "passive"))
      (node (ref "R6") (pin "1") (pinfunction "1_1") (pintype "passive"))
      (node (ref "U8") (pin "4") (pinfunction "~{INT}_4") (pintype "output"))
    )
    (net (code "67") (name "RTC_PS_EN") (class "Default")
      (node (ref "Q1") (pin "3") (pinfunction "D_3") (pintype "passive"))
      (node (ref "U9") (pin "5") (pinfunction "A2_5") (pintype "passive"))
    )
    (net (code "68") (name "SIM_CLK") (class "Default")
      (node (ref "J6") (pin "S3") (pinfunction "CLK_S3") (pintype "input"))
      (node (ref "TP3") (pin "TP") (pinfunction "TP_TP") (pintype "input"))
      (node (ref "U1") (pin "46") (pinfunction "SIM_CLK_46") (pintype "bidirectional"))
    )
    (net (code "69") (name "SIM_DET") (class "Default")
      (node (ref "U1") (pin "45") (pinfunction "SIM_DET_45") (pintype "bidirectional"))
    )
    (net (code "70") (name "SIM_IO") (class "Default")
      (node (ref "J6") (pin "S6") (pinfunction "I/O_S6") (pintype "bidirectional"))
      (node (ref "TP6") (pin "TP") (pinfunction "TP_TP") (pintype "input"))
      (node (ref "U1") (pin "48") (pinfunction "SIM_IO_48") (pintype "bidirectional"))
    )
    (net (code "71") (name "SIM_RST") (class "Default")
      (node (ref "J6") (pin "S2") (pinfunction "RST_S2") (pintype "input"))
      (node (ref "TP4") (pin "TP") (pinfunction "TP_TP") (pintype "input"))
      (node (ref "U1") (pin "43") (pinfunction "SIM_RST_43") (pintype "bidirectional"))
    )
    (net (code "72") (name "SIM_VCC") (class "Default")
      (node (ref "J6") (pin "S1") (pinfunction "VCC_S1") (pintype "power_in"))
      (node (ref "TP5") (pin "TP") (pinfunction "TP_TP") (pintype "input"))
      (node (ref "U1") (pin "49") (pinfunction "SIM_1V8_49") (pintype "power_in"))
    )
    (net (code "73") (name "SWCLK") (class "Default")
      (node (ref "J8") (pin "4") (pinfunction "SWDCLK_4") (pintype "bidirectional"))
      (node (ref "TP2") (pin "TP") (pinfunction "TP_TP") (pintype "input"))
      (node (ref "U1") (pin "33") (pinfunction "SWDCLK_33") (pintype "input"))
    )
    (net (code "74") (name "SWDIO") (class "Default")
      (node (ref "J8") (pin "2") (pinfunction "SWDIO_2") (pintype "bidirectional"))
      (node (ref "TP1") (pin "TP") (pinfunction "TP_TP") (pintype "input"))
      (node (ref "U1") (pin "34") (pinfunction "SWDIO_34") (pintype "bidirectional"))
    )
    (net (code "75") (name "VBAT") (class "Default")
      (node (ref "J2") (pin "1") (pinfunction "1_1") (pintype "bidirectional"))
      (node (ref "J5") (pin "2") (pinfunction "+_2") (pintype "bidirectional"))
      (node (ref "Q2") (pin "4") (pinfunction "S_4") (pintype "passive"))
      (node (ref "Q3") (pin "3") (pinfunction "D_3") (pintype "passive"))
      (node (ref "R10") (pin "2") (pinfunction "2_2") (pintype "passive"))
      (node (ref "U2") (pin "3") (pinfunction "VBAT_3") (pintype "power_in"))
    )
    (net (code "76") (name "VBUS") (class "Default")
      (node (ref "C11") (pin "1") (pinfunction "1_1") (pintype "passive"))
      (node (ref "C13") (pin "1") (pinfunction "1_1") (pintype "passive"))
      (node (ref "C14") (pin "1") (pinfunction "1_1") (pintype "passive"))
      (node (ref "D5") (pin "A") (pinfunction "A_A") (pintype "passive"))
      (node (ref "D6") (pin "A") (pinfunction "A_A") (pintype "passive"))
      (node (ref "J1") (pin "VBUS1") (pinfunction "VBUS_VBUS1") (pintype "bidirectional"))
      (node (ref "J1") (pin "VBUS2") (pinfunction "VBUS_VBUS2") (pintype "bidirectional"))
      (node (ref "Q3") (pin "1") (pinfunction "G_1") (pintype "passive"))
      (node (ref "R15") (pin "2") (pinfunction "2_2") (pintype "passive"))
      (node (ref "R7") (pin "2") (pinfunction "2_2") (pintype "passive"))
      (node (ref "U2") (pin "4") (pinfunction "VIN_4") (pintype "power_in"))
      (node (ref "U5") (pin "7") (pinfunction "VREGIN_7") (pintype "input"))
      (node (ref "U9") (pin "2") (pinfunction "A2_2") (pintype "passive"))
    )
    (net (code "77") (name "VCC_5V0") (class "Default")
      (node (ref "D5") (pin "C") (pinfunction "C_C") (pintype "passive"))
      (node (ref "J2") (pin "3") (pinfunction "3_3") (pintype "bidirectional"))
    )
    (net (code "78") (name "VIO") (class "Default")
      (node (ref "U1") (pin "57") (pinfunction "VIO_57") (pintype "power_in"))
    )
    (net (code "79") (name "VPP") (class "Default")
      (node (ref "J6") (pin "S5") (pinfunction "VPP_S5") (pintype "power_in"))
    )
    (net (code "80") (name "VSYS") (class "Default")
      (node (ref "C17") (pin "1") (pinfunction "1_1") (pintype "passive"))
      (node (ref "C6") (pin "1") (pinfunction "1_1") (pintype "passive"))
      (node (ref "C7") (pin "1") (pinfunction "1_1") (pintype "passive"))
      (node (ref "D6") (pin "C") (pinfunction "C_C") (pintype "passive"))
      (node (ref "JMP2") (pin "P$1") (pinfunction "1_P$1") (pintype "passive"))
      (node (ref "Q1") (pin "2") (pinfunction "S_2") (pintype "passive"))
      (node (ref "Q3") (pin "2") (pinfunction "S_2") (pintype "passive"))
      (node (ref "R6") (pin "2") (pinfunction "2_2") (pintype "passive"))
      (node (ref "SW2") (pin "1") (pinfunction "1_1") (pintype "passive"))
      (node (ref "SW2") (pin "2") (pinfunction "1_2") (pintype "passive"))
      (node (ref "U3") (pin "5") (pinfunction "VIN_5") (pintype "power_in"))
      (node (ref "U3") (pin "7") (pinfunction "PS_SYNC_7") (pintype "input"))
      (node (ref "U3") (pin "8") (pinfunction "VINA_8") (pintype "power_in"))
      (node (ref "U8") (pin "10") (pinfunction "VDD_10") (pintype "power_in"))
    )
    (net (code "81") (name "unconnected-(J5-PAD1-PadNC1)") (class "Default")
      (node (ref "J5") (pin "NC1") (pinfunction "PAD1_NC1") (pintype "bidirectional"))
    )
    (net (code "82") (name "unconnected-(J5-PAD2-PadNC2)") (class "Default")
      (node (ref "J5") (pin "NC2") (pinfunction "PAD2_NC2") (pintype "bidirectional"))
    )
    (net (code "83") (name "unconnected-(J8-SWO-Pad6)") (class "Default")
      (node (ref "J8") (pin "6") (pinfunction "SWO_6") (pintype "bidirectional"))
    )
    (net (code "84") (name "unconnected-(J8-~{RST}-Pad10)") (class "Default")
      (node (ref "J8") (pin "10") (pinfunction "~{RST}_10") (pintype "bidirectional"))
    )
    (net (code "85") (name "unconnected-(U1-AUX-Pad64)") (class "Default")
      (node (ref "U1") (pin "64") (pinfunction "AUX_64") (pintype "output"))
    )
    (net (code "86") (name "unconnected-(U1-COEX1-Pad92)") (class "Default")
      (node (ref "U1") (pin "92") (pinfunction "COEX1_92") (pintype "bidirectional"))
    )
    (net (code "87") (name "unconnected-(U1-COEX2-Pad91)") (class "Default")
      (node (ref "U1") (pin "91") (pinfunction "COEX2_91") (pintype "bidirectional"))
    )
    (net (code "88") (name "unconnected-(U1-MAGPIO0-Pad55)") (class "Default")
      (node (ref "U1") (pin "55") (pinfunction "MAGPIO0_55") (pintype "bidirectional"))
    )
    (net (code "89") (name "unconnected-(U1-MAGPIO1-Pad54)") (class "Default")
      (node (ref "U1") (pin "54") (pinfunction "MAGPIO1_54") (pintype "bidirectional"))
    )
    (net (code "90") (name "unconnected-(U1-MAGPIO2-Pad53)") (class "Default")
      (node (ref "U1") (pin "53") (pinfunction "MAGPIO2_53") (pintype "bidirectional"))
    )
    (net (code "91") (name "unconnected-(U1-SCLK-Pad58)") (class "Default")
      (node (ref "U1") (pin "58") (pinfunction "SCLK_58") (pintype "bidirectional"))
    )
    (net (code "92") (name "unconnected-(U1-SDATA-Pad59)") (class "Default")
      (node (ref "U1") (pin "59") (pinfunction "SDATA_59") (pintype "bidirectional"))
    )
    (net (code "93") (name "unconnected-(U5-GPIO.0{slash}TXT-Pad14)") (class "Default")
      (node (ref "U5") (pin "14") (pinfunction "GPIO.0/TXT_14") (pintype "bidirectional"))
    )
    (net (code "94") (name "unconnected-(U5-GPIO.1{slash}RXT-Pad13)") (class "Default")
      (node (ref "U5") (pin "13") (pinfunction "GPIO.1/RXT_13") (pintype "bidirectional"))
    )
    (net (code "95") (name "unconnected-(U5-GPIO.2{slash}RS485-Pad12)") (class "Default")
      (node (ref "U5") (pin "12") (pinfunction "GPIO.2/RS485_12") (pintype "bidirectional"))
    )
    (net (code "96") (name "unconnected-(U5-GPIO.3{slash}WAKEUP-Pad11)") (class "Default")
      (node (ref "U5") (pin "11") (pinfunction "GPIO.3/WAKEUP_11") (pintype "bidirectional"))
    )
    (net (code "97") (name "unconnected-(U5-SUSPEND-Pad17)") (class "Default")
      (node (ref "U5") (pin "17") (pinfunction "SUSPEND_17") (pintype "output"))
    )
    (net (code "98") (name "unconnected-(U5-SUSPENDB-Pad15)") (class "Default")
      (node (ref "U5") (pin "15") (pinfunction "SUSPENDB_15") (pintype "output"))
    )
    (net (code "99") (name "unconnected-(U5-~{CTS}-Pad18)") (class "Default")
      (node (ref "U5") (pin "18") (pinfunction "~{CTS}_18") (pintype "input"))
    )
    (net (code "100") (name "unconnected-(U5-~{DCD}-Pad24)") (class "Default")
      (node (ref "U5") (pin "24") (pinfunction "~{DCD}_24") (pintype "input"))
    )
    (net (code "101") (name "unconnected-(U5-~{DSR}-Pad22)") (class "Default")
      (node (ref "U5") (pin "22") (pinfunction "~{DSR}_22") (pintype "input"))
    )
    (net (code "102") (name "unconnected-(U5-~{DTR}-Pad23)") (class "Default")
      (node (ref "U5") (pin "23") (pinfunction "~{DTR}_23") (pintype "output"))
    )
    (net (code "103") (name "unconnected-(U5-~{RI}{slash}CLK-Pad1)") (class "Default")
      (node (ref "U5") (pin "1") (pinfunction "~{RI}/CLK_1") (pintype "bidirectional"))
    )
    (net (code "104") (name "unconnected-(U5-~{RTS}-Pad19)") (class "Default")
      (node (ref "U5") (pin "19") (pinfunction "~{RTS}_19") (pintype "output"))
    )
    (net (code "105") (name "unconnected-(U8-CLKOUT-Pad9)") (class "Default")
      (node (ref "U8") (pin "9") (pinfunction "CLKOUT_9") (pintype "output"))
    )
    (net (code "106") (name "unconnected-(U12-INT2-Pad11)") (class "Default")
      (node (ref "U12") (pin "11") (pinfunction "INT2_11") (pintype "output"))
    )
    (net (code "107") (name "~{EN}") (class "Default")
      (node (ref "J2") (pin "2") (pinfunction "2_2") (pintype "bidirectional"))
      (node (ref "Q5") (pin "1") (pinfunction "G_1") (pintype "bidirectional"))
      (node (ref "R19") (pin "2") (pinfunction "2_2") (pintype "passive"))
    )
    (net (code "108") (name "~{RESET}") (class "Default")
      (node (ref "J3") (pin "1") (pinfunction "1_1") (pintype "bidirectional"))
      (node (ref "SW1") (pin "1") (pinfunction "1_1") (pintype "passive"))
      (node (ref "SW1") (pin "2") (pinfunction "1_2") (pintype "passive"))
      (node (ref "U1") (pin "32") (pinfunction "NRESET_32") (pintype "input"))
    )
  )
)
